# Control_Connector.net
KiCad netlist of a schematic drawn in Altium Designer
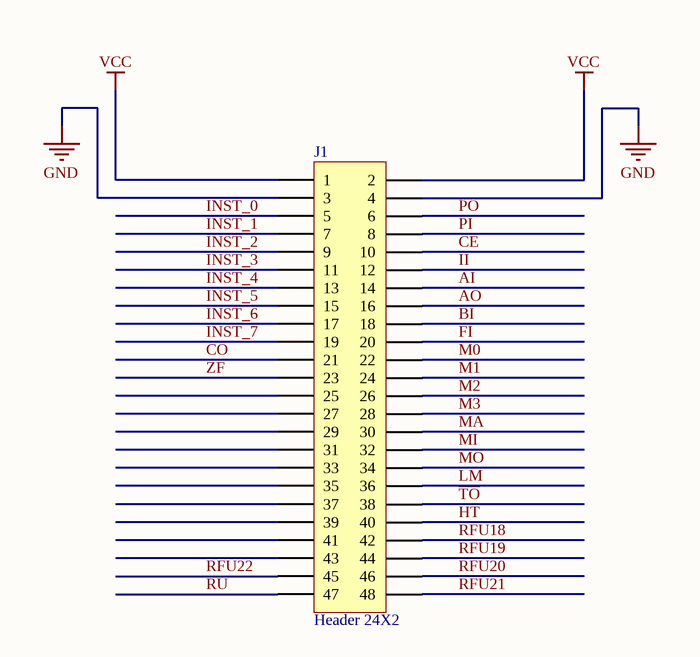
[diagram p0: Control Connector.SchDoc]

(export (version "E")
  (design (tool "Eeschema 10.0.6"))
  (components
    (comp (ref "J1")
      (value "Header 24X2")
      (footprint "HDR2X24")
      (description "Header, 24-Pin, Dual row")
      (fields (field (name "PUBLISHER") "Altium Limited"))
      (libsource (lib "Miscellaneous Connectors") (part "Header 24X2"))
    )
  )
  (nets
    (net (code "1") (name "/CO") (class "Default")
      (node (ref "J1") (pin "21") (pinfunction "21_21") (pintype "passive"))
    )
    (net (code "2") (name "/HT") (class "Default")
      (node (ref "J1") (pin "40") (pinfunction "40_40") (pintype "passive"))
    )
    (net (code "3") (name "/INST_0") (class "Default")
      (node (ref "J1") (pin "5") (pinfunction "5_5") (pintype "passive"))
    )
    (net (code "4") (name "/INST_1") (class "Default")
      (node (ref "J1") (pin "7") (pinfunction "7_7") (pintype "passive"))
    )
    (net (code "5") (name "/INST_2") (class "Default")
      (node (ref "J1") (pin "9") (pinfunction "9_9") (pintype "passive"))
    )
    (net (code "6") (name "/INST_3") (class "Default")
      (node (ref "J1") (pin "11") (pinfunction "11_11") (pintype "passive"))
    )
    (net (code "7") (name "/INST_4") (class "Default")
      (node (ref "J1") (pin "13") (pinfunction "13_13") (pintype "passive"))
    )
    (net (code "8") (name "/INST_5") (class "Default")
      (node (ref "J1") (pin "15") (pinfunction "15_15") (pintype "passive"))
    )
    (net (code "9") (name "/INST_6") (class "Default")
      (node (ref "J1") (pin "17") (pinfunction "17_17") (pintype "passive"))
    )
    (net (code "10") (name "/INST_7") (class "Default")
      (node (ref "J1") (pin "19") (pinfunction "19_19") (pintype "passive"))
    )
    (net (code "11") (name "/LM") (class "Default")
      (node (ref "J1") (pin "36") (pinfunction "36_36") (pintype "passive"))
    )
    (net (code "12") (name "/M0") (class "Default")
      (node (ref "J1") (pin "22") (pinfunction "22_22") (pintype "passive"))
    )
    (net (code "13") (name "/M1") (class "Default")
      (node (ref "J1") (pin "24") (pinfunction "24_24") (pintype "passive"))
    )
    (net (code "14") (name "/M2") (class "Default")
      (node (ref "J1") (pin "26") (pinfunction "26_26") (pintype "passive"))
    )
    (net (code "15") (name "/M3") (class "Default")
      (node (ref "J1") (pin "28") (pinfunction "28_28") (pintype "passive"))
    )
    (net (code "16") (name "/MI") (class "Default")
      (node (ref "J1") (pin "32") (pinfunction "32_32") (pintype "passive"))
    )
    (net (code "17") (name "/RFU18") (class "Default")
      (node (ref "J1") (pin "42") (pinfunction "42_42") (pintype "passive"))
    )
    (net (code "18") (name "/RFU19") (class "Default")
      (node (ref "J1") (pin "44") (pinfunction "44_44") (pintype "passive"))
    )
    (net (code "19") (name "/RFU20") (class "Default")
      (node (ref "J1") (pin "46") (pinfunction "46_46") (pintype "passive"))
    )
    (net (code "20") (name "/RFU21") (class "Default")
      (node (ref "J1") (pin "48") (pinfunction "48_48") (pintype "passive"))
    )
    (net (code "21") (name "/RFU22") (class "Default")
      (node (ref "J1") (pin "45") (pinfunction "45_45") (pintype "passive"))
    )
    (net (code "22") (name "/RU") (class "Default")
      (node (ref "J1") (pin "47") (pinfunction "47_47") (pintype "passive"))
    )
    (net (code "23") (name "/ZF") (class "Default")
      (node (ref "J1") (pin "23") (pinfunction "23_23") (pintype "passive"))
    )
    (net (code "24") (name "/~{AI}") (class "Default")
      (node (ref "J1") (pin "14") (pinfunction "14_14") (pintype "passive"))
    )
    (net (code "25") (name "/~{AO}") (class "Default")
      (node (ref "J1") (pin "16") (pinfunction "16_16") (pintype "passive"))
    )
    (net (code "26") (name "/~{BI}") (class "Default")
      (node (ref "J1") (pin "18") (pinfunction "18_18") (pintype "passive"))
    )
    (net (code "27") (name "/~{CE}") (class "Default")
      (node (ref "J1") (pin "10") (pinfunction "10_10") (pintype "passive"))
    )
    (net (code "28") (name "/~{FI}") (class "Default")
      (node (ref "J1") (pin "20") (pinfunction "20_20") (pintype "passive"))
    )
    (net (code "29") (name "/~{II}") (class "Default")
      (node (ref "J1") (pin "12") (pinfunction "12_12") (pintype "passive"))
    )
    (net (code "30") (name "/~{MA}") (class "Default")
      (node (ref "J1") (pin "30") (pinfunction "30_30") (pintype "passive"))
    )
    (net (code "31") (name "/~{MO}") (class "Default")
      (node (ref "J1") (pin "34") (pinfunction "34_34") (pintype "passive"))
    )
    (net (code "32") (name "/~{PI}") (class "Default")
      (node (ref "J1") (pin "8") (pinfunction "8_8") (pintype "passive"))
    )
    (net (code "33") (name "/~{PO}") (class "Default")
      (node (ref "J1") (pin "6") (pinfunction "6_6") (pintype "passive"))
    )
    (net (code "34") (name "/~{TO}") (class "Default")
      (node (ref "J1") (pin "38") (pinfunction "38_38") (pintype "passive"))
    )
    (net (code "35") (name "GND") (class "Default")
      (node (ref "J1") (pin "3") (pinfunction "3_3") (pintype "passive"))
      (node (ref "J1") (pin "4") (pinfunction "4_4") (pintype "passive"))
    )
    (net (code "36") (name "VCC") (class "Default")
      (node (ref "J1") (pin "1") (pinfunction "1_1") (pintype "passive"))
      (node (ref "J1") (pin "2") (pinfunction "2_2") (pintype "passive"))
    )
    (net (code "37") (name "unconnected-(J1-Pad25)") (class "Default")
      (node (ref "J1") (pin "25") (pinfunction "25_25") (pintype "passive"))
    )
    (net (code "38") (name "unconnected-(J1-Pad27)") (class "Default")
      (node (ref "J1") (pin "27") (pinfunction "27_27") (pintype "passive"))
    )
    (net (code "39") (name "unconnected-(J1-Pad29)") (class "Default")
      (node (ref "J1") (pin "29") (pinfunction "29_29") (pintype "passive"))
    )
    (net (code "40") (name "unconnected-(J1-Pad31)") (class "Default")
      (node (ref "J1") (pin "31") (pinfunction "31_31") (pintype "passive"))
    )
    (net (code "41") (name "unconnected-(J1-Pad33)") (class "Default")
      (node (ref "J1") (pin "33") (pinfunction "33_33") (pintype "passive"))
    )
    (net (code "42") (name "unconnected-(J1-Pad35)") (class "Default")
      (node (ref "J1") (pin "35") (pinfunction "35_35") (pintype "passive"))
    )
    (net (code "43") (name "unconnected-(J1-Pad37)") (class "Default")
      (node (ref "J1") (pin "37") (pinfunction "37_37") (pintype "passive"))
    )
    (net (code "44") (name "unconnected-(J1-Pad39)") (class "Default")
      (node (ref "J1") (pin "39") (pinfunction "39_39") (pintype "passive"))
    )
    (net (code "45") (name "unconnected-(J1-Pad41)") (class "Default")
      (node (ref "J1") (pin "41") (pinfunction "41_41") (pintype "passive"))
    )
    (net (code "46") (name "unconnected-(J1-Pad43)") (class "Default")
      (node (ref "J1") (pin "43") (pinfunction "43_43") (pintype "passive"))
    )
  )
)
